# CyberAss.net
KiCad netlist of a schematic drawn in Altium Designer
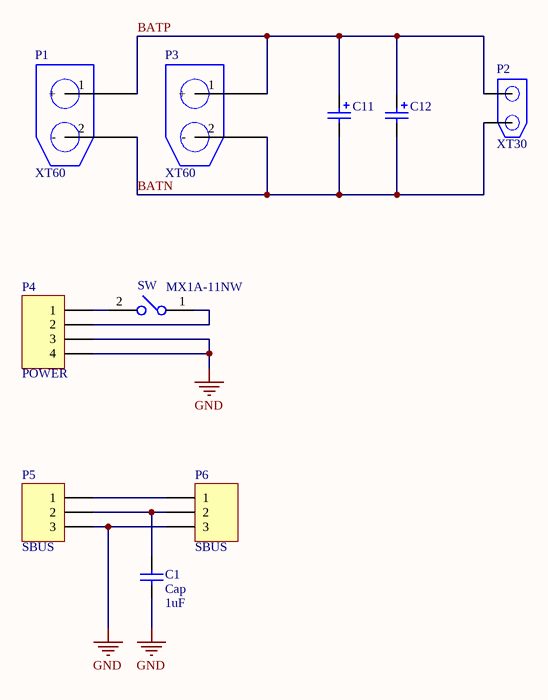
[diagram p0: CyberAss.SchDoc]

(export (version "E")
  (design (tool "Eeschema 10.0.6"))
  (components
    (comp (ref "C1")
      (value "Cap")
      (footprint "6-0805_M")
      (description "Capacitor")
      (fields (field (name "ALTIUM_VALUE") "1uF") (field (name "PUBLISHER") "Altium Limited"))
      (libsource (lib "Miscellaneous Devices") (part "Cap"))
    )
    (comp (ref "C11")
      (value "35V 47uf")
      (footprint "C3528")
      (description "Polarized Capacitor (Axial)")
      (fields (field (name "PUBLISHER") "Altium Limited"))
      (libsource (lib "Miscellaneous Devices") (part "Cap Pol2"))
    )
    (comp (ref "C12")
      (value "35V 47uf")
      (footprint "C3528")
      (description "Polarized Capacitor (Axial)")
      (fields (field (name "PUBLISHER") "Altium Limited"))
      (libsource (lib "Miscellaneous Devices") (part "Cap Pol2"))
    )
    (comp (ref "P1") (value "XT60") (footprint "XT60") (libsource (lib "Schlib1") (part "XT60")))
    (comp (ref "P2") (value "XT30") (footprint "XT30") (libsource (lib "T12Power") (part "XT30")))
    (comp (ref "P3") (value "XT60") (footprint "XT60") (libsource (lib "Schlib1") (part "XT60")))
    (comp (ref "P4")
      (value "POWER")
      (footprint "SS1.0-2p")
      (description "Header, 4-Pin")
      (fields (field (name "PUBLISHER") "Altium Limited"))
      (libsource (lib "Miscellaneous Connectors") (part "Header 4"))
    )
    (comp (ref "P5")
      (value "SBUS")
      (footprint "XH2.54-3p")
      (description "Header, 3-Pin")
      (fields (field (name "PUBLISHER") "Altium Limited"))
      (libsource (lib "Miscellaneous Connectors") (part "Header 3"))
    )
    (comp (ref "P6")
      (value "SBUS")
      (footprint "HDR1X3")
      (description "Header, 3-Pin")
      (fields (field (name "PUBLISHER") "Altium Limited"))
      (libsource (lib "") (part "Header 3_1"))
    )
    (comp (ref "SW")
      (value "Switch_Cherry_MX1A-11NW_eec")
      (footprint "Cherry_MX1A-11NW_0")
      (description "SWITCH Pushbutton Switch SPST-NO Keyswitch Through Hole")
      (fields
        (field (name "PART NUMBER") "MX1A-11NW")
        (field (name "MANUFACTURER") "Cherry")
        (field (name "MOUSER PART NUMBER") "540-MX1A-11NW")
      )
      (libsource (lib "Switch_Cherry_MX1A-11NW_eec") (part "Switch_Cherry_MX1A-11NW_eec"))
    )
  )
  (nets
    (net (code "1") (name "/BATN") (class "Default")
      (node (ref "C11") (pin "2") (pinfunction "2_2") (pintype "passive"))
      (node (ref "C12") (pin "2") (pinfunction "2_2") (pintype "passive"))
      (node (ref "P1") (pin "2") (pinfunction "-_2") (pintype "passive"))
      (node (ref "P2") (pin "2") (pinfunction "-_2") (pintype "passive"))
      (node (ref "P3") (pin "2") (pinfunction "-_2") (pintype "passive"))
    )
    (net (code "2") (name "/BATP") (class "Default")
      (node (ref "C11") (pin "1") (pinfunction "1_1") (pintype "passive"))
      (node (ref "C12") (pin "1") (pinfunction "1_1") (pintype "passive"))
      (node (ref "P1") (pin "1") (pinfunction "+_1") (pintype "passive"))
      (node (ref "P2") (pin "1") (pinfunction "+_1") (pintype "passive"))
      (node (ref "P3") (pin "1") (pinfunction "+_1") (pintype "passive"))
    )
    (net (code "3") (name "GND") (class "Default")
      (node (ref "C1") (pin "1") (pinfunction "1_1") (pintype "passive"))
      (node (ref "P4") (pin "3") (pinfunction "3_3") (pintype "passive"))
      (node (ref "P4") (pin "4") (pinfunction "4_4") (pintype "passive"))
      (node (ref "P5") (pin "3") (pinfunction "3_3") (pintype "passive"))
      (node (ref "P6") (pin "3") (pinfunction "3_3") (pintype "passive"))
    )
    (net (code "4") (name "Net-(C1-Pad2)") (class "Default")
      (node (ref "C1") (pin "2") (pinfunction "2_2") (pintype "passive"))
      (node (ref "P5") (pin "2") (pinfunction "2_2") (pintype "passive"))
      (node (ref "P6") (pin "2") (pinfunction "2_2") (pintype "passive"))
    )
    (net (code "5") (name "Net-(P4-Pad1)") (class "Default")
      (node (ref "P4") (pin "1") (pinfunction "1_1") (pintype "passive"))
      (node (ref "SW") (pin "2") (pinfunction "2_2") (pintype "passive"))
    )
    (net (code "6") (name "Net-(P4-Pad2)") (class "Default")
      (node (ref "P4") (pin "2") (pinfunction "2_2") (pintype "passive"))
      (node (ref "SW") (pin "1") (pinfunction "1_1") (pintype "passive"))
    )
    (net (code "7") (name "Net-(P5-Pad1)") (class "Default")
      (node (ref "P5") (pin "1") (pinfunction "1_1") (pintype "passive"))
      (node (ref "P6") (pin "1") (pinfunction "1_1") (pintype "passive"))
    )
  )
)
